# Schematic_easyeda.net
KiCad netlist of a schematic drawn in EasyEDA
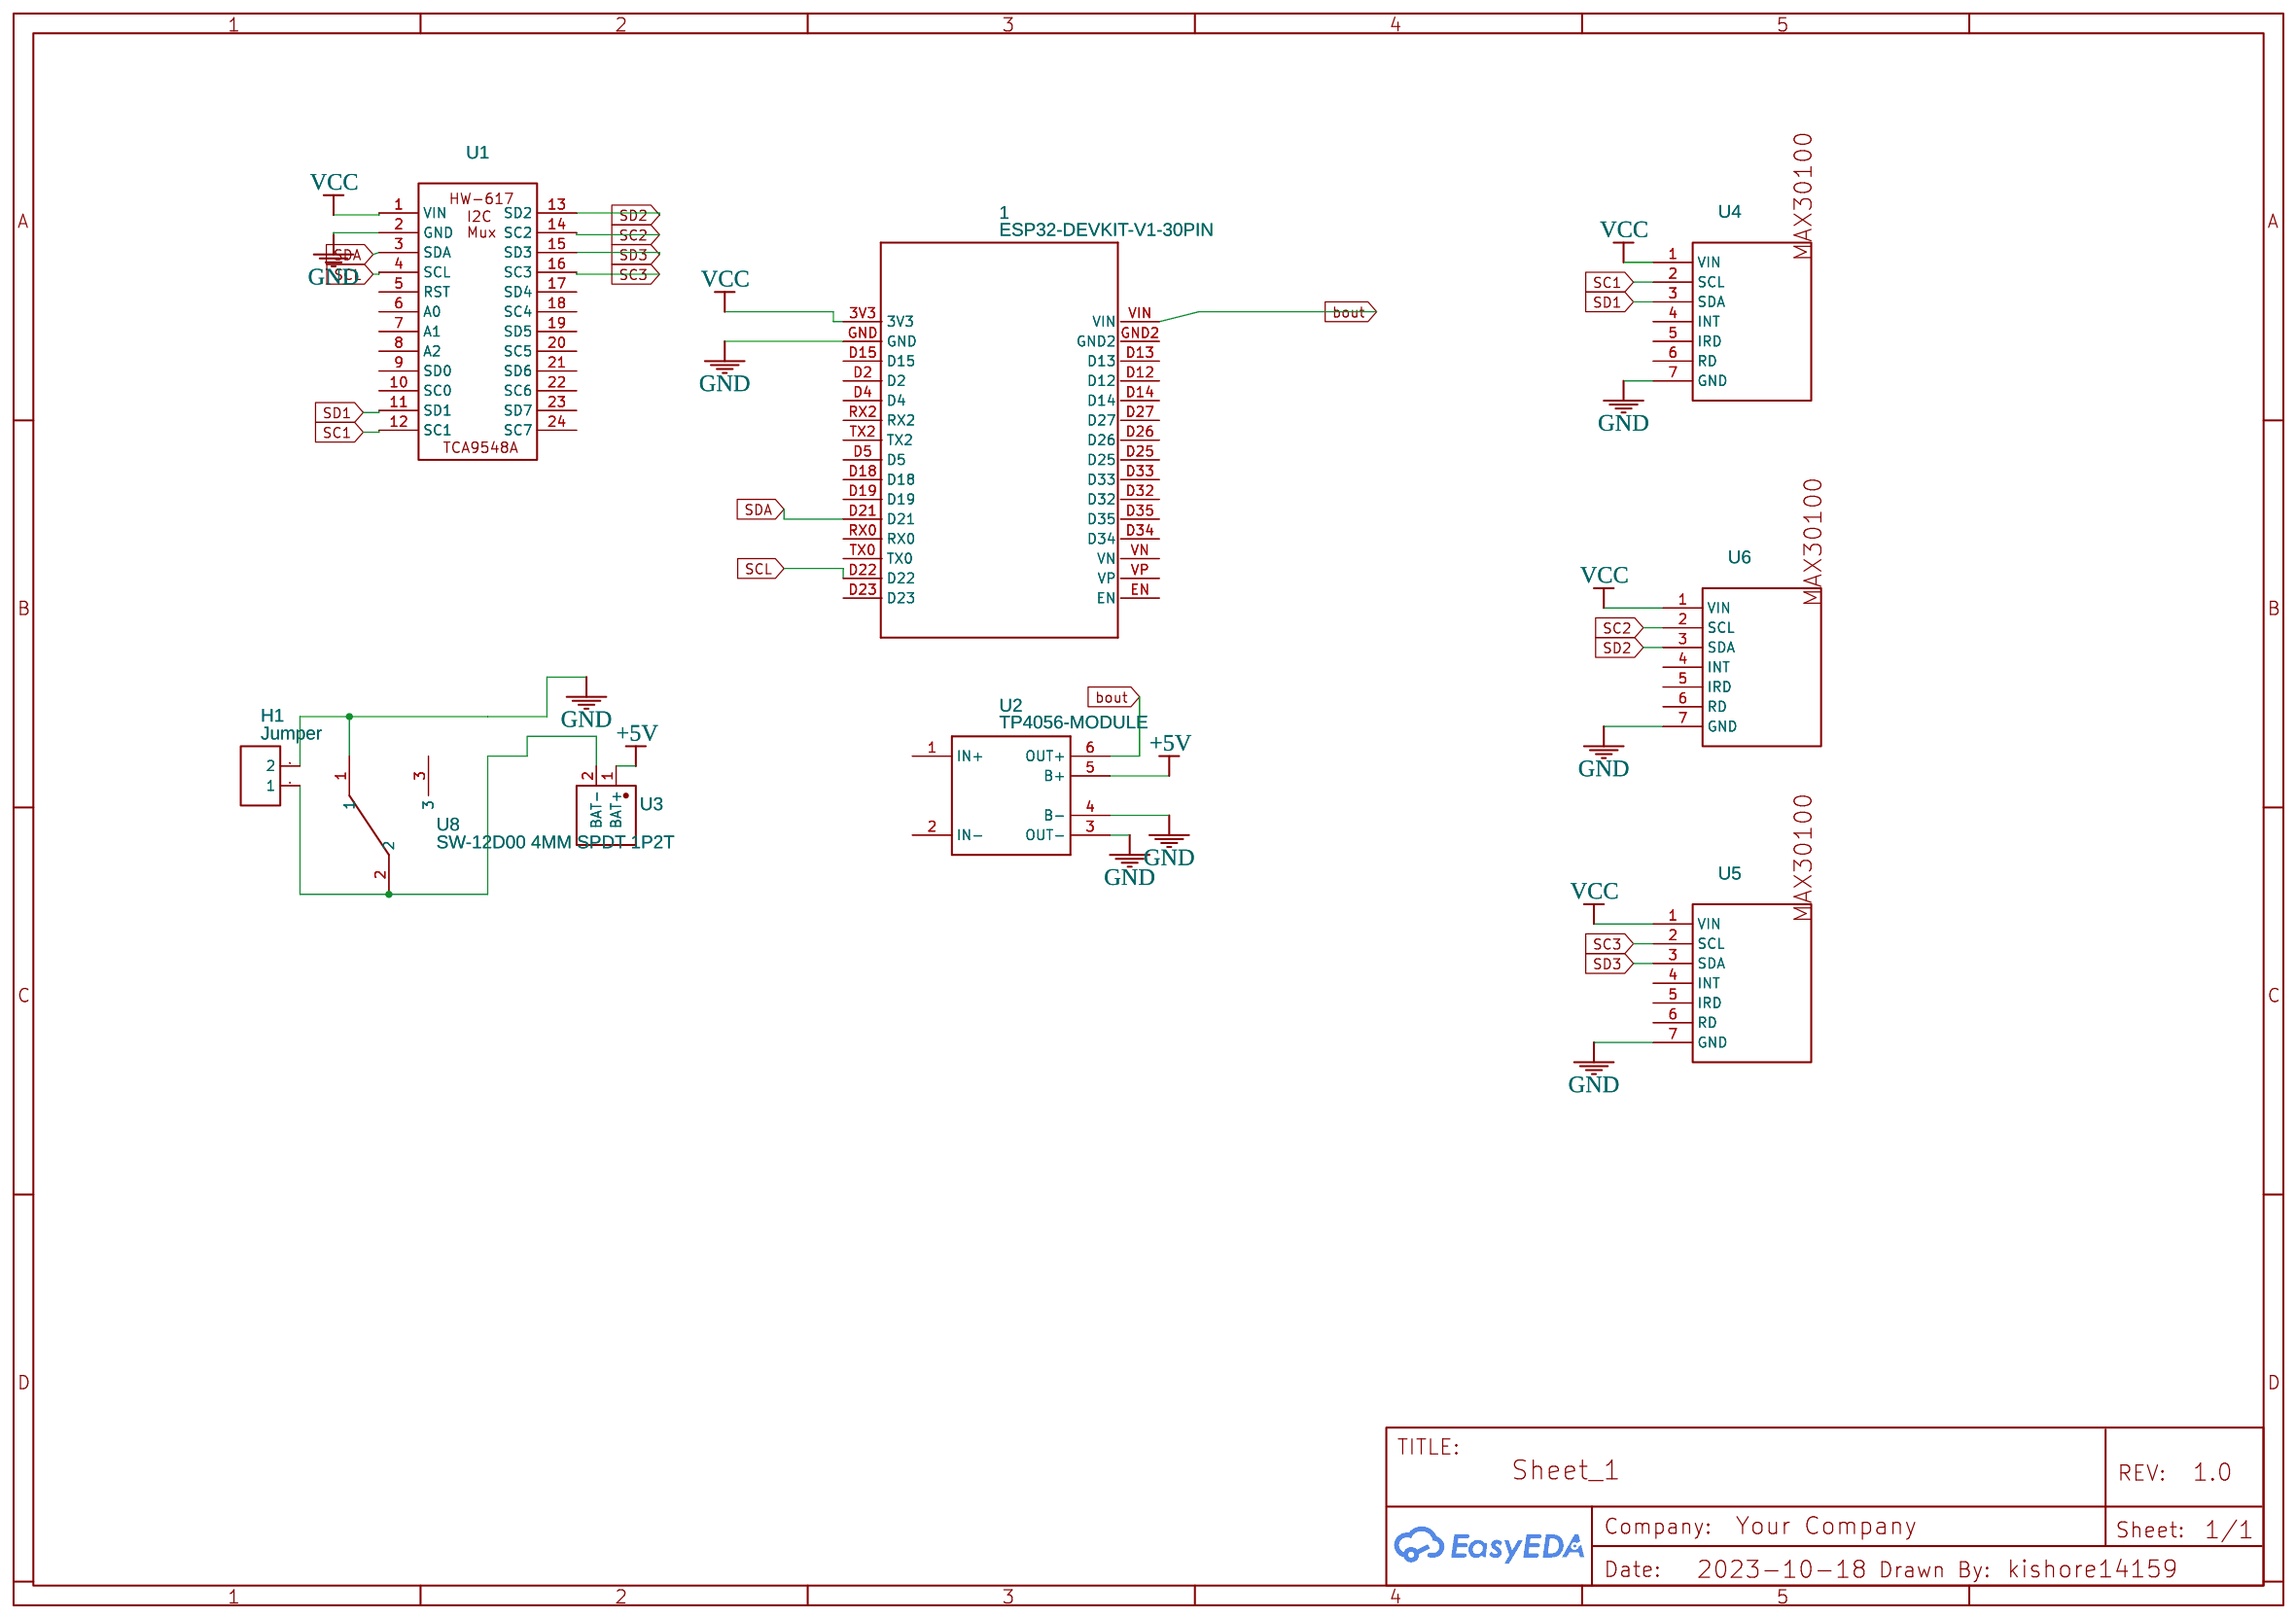
[diagram p0: schematic sheet]

(export (version "E")
  (design (tool "Eeschema 10.0.6"))
  (components
    (comp (ref "1") (value "ESP32-DEVKIT-V1-30PIN") (libsource (lib "") (part "ESP32-DEVKIT-V1-30PIN")))
    (comp (ref "H1") (value "Jumper") (libsource (lib "") (part "HDR-F-2.54_1x2")))
    (comp (ref "U1")
      (value "NO")
      (fields (field (name "Manufacturer Part") "TCA9548A") (field (name "Manufacturer") "Texas Instruments"))
      (libsource (lib "") (part "TCA9548A HW-617_OK"))
    )
    (comp (ref "U2") (value "TP4056-MODULE") (libsource (lib "") (part "TP4056-MODULE")))
    (comp (ref "U3") (value "NO") (libsource (lib "") (part "JST-PH-JST-PH2")))
    (comp (ref "U4") (value "NO") (libsource (lib "") (part "MAX30100 MODULE")))
    (comp (ref "U5") (value "NO") (libsource (lib "") (part "MAX30100 MODULE")))
    (comp (ref "U6") (value "NO") (libsource (lib "") (part "MAX30100 MODULE")))
    (comp (ref "U8") (value "SW-12D00 4MM SPDT 1P2T") (libsource (lib "") (part "SW-12D00 4MM SPDT 1P2T")))
  )
  (nets
    (net (code "1") (name "+5V") (class "Default")
      (node (ref "U2") (pin "5") (pinfunction "B+_5") (pintype "passive"))
      (node (ref "U3") (pin "1") (pinfunction "BAT+_1") (pintype "unspecified"))
    )
    (net (code "2") (name "GND") (class "Default")
      (node (ref "1") (pin "GND") (pinfunction "GND_GND") (pintype "bidirectional"))
      (node (ref "H1") (pin "2") (pinfunction "2_2") (pintype "input"))
      (node (ref "U1") (pin "2") (pinfunction "GND_2") (pintype "unspecified"))
      (node (ref "U2") (pin "3") (pinfunction "OUT-_3") (pintype "passive"))
      (node (ref "U2") (pin "4") (pinfunction "B-_4") (pintype "passive"))
      (node (ref "U4") (pin "7") (pinfunction "GND_7") (pintype "unspecified"))
      (node (ref "U5") (pin "7") (pinfunction "GND_7") (pintype "unspecified"))
      (node (ref "U6") (pin "7") (pinfunction "GND_7") (pintype "unspecified"))
      (node (ref "U8") (pin "1") (pinfunction "1_1") (pintype "unspecified"))
    )
    (net (code "3") (name "Net-(U3-BAT-)") (class "Default")
      (node (ref "H1") (pin "1") (pinfunction "1_1") (pintype "input"))
      (node (ref "U3") (pin "2") (pinfunction "BAT-_2") (pintype "unspecified"))
      (node (ref "U8") (pin "2") (pinfunction "2_2") (pintype "unspecified"))
    )
    (net (code "4") (name "SC1") (class "Default")
      (node (ref "U1") (pin "12") (pinfunction "SC1_12") (pintype "unspecified"))
      (node (ref "U4") (pin "2") (pinfunction "SCL_2") (pintype "unspecified"))
    )
    (net (code "5") (name "SC2") (class "Default")
      (node (ref "U1") (pin "14") (pinfunction "SC2_14") (pintype "unspecified"))
      (node (ref "U6") (pin "2") (pinfunction "SCL_2") (pintype "unspecified"))
    )
    (net (code "6") (name "SC3") (class "Default")
      (node (ref "U1") (pin "16") (pinfunction "SC3_16") (pintype "unspecified"))
      (node (ref "U5") (pin "2") (pinfunction "SCL_2") (pintype "unspecified"))
    )
    (net (code "7") (name "SCL") (class "Default")
      (node (ref "1") (pin "D22") (pinfunction "D22_D22") (pintype "bidirectional"))
      (node (ref "U1") (pin "4") (pinfunction "SCL_4") (pintype "unspecified"))
    )
    (net (code "8") (name "SD1") (class "Default")
      (node (ref "U1") (pin "11") (pinfunction "SD1_11") (pintype "unspecified"))
      (node (ref "U4") (pin "3") (pinfunction "SDA_3") (pintype "unspecified"))
    )
    (net (code "9") (name "SD2") (class "Default")
      (node (ref "U1") (pin "13") (pinfunction "SD2_13") (pintype "unspecified"))
      (node (ref "U6") (pin "3") (pinfunction "SDA_3") (pintype "unspecified"))
    )
    (net (code "10") (name "SD3") (class "Default")
      (node (ref "U1") (pin "15") (pinfunction "SD3_15") (pintype "unspecified"))
      (node (ref "U5") (pin "3") (pinfunction "SDA_3") (pintype "unspecified"))
    )
    (net (code "11") (name "SDA") (class "Default")
      (node (ref "1") (pin "D21") (pinfunction "D21_D21") (pintype "bidirectional"))
      (node (ref "U1") (pin "3") (pinfunction "SDA_3") (pintype "unspecified"))
    )
    (net (code "12") (name "VCC") (class "Default")
      (node (ref "1") (pin "3V3") (pinfunction "3V3_3V3") (pintype "bidirectional"))
      (node (ref "U1") (pin "1") (pinfunction "VIN_1") (pintype "unspecified"))
      (node (ref "U4") (pin "1") (pinfunction "VIN_1") (pintype "unspecified"))
      (node (ref "U5") (pin "1") (pinfunction "VIN_1") (pintype "unspecified"))
      (node (ref "U6") (pin "1") (pinfunction "VIN_1") (pintype "unspecified"))
    )
    (net (code "13") (name "bout") (class "Default")
      (node (ref "1") (pin "VIN") (pinfunction "VIN_VIN") (pintype "bidirectional"))
      (node (ref "U2") (pin "6") (pinfunction "OUT+_6") (pintype "passive"))
    )
    (net (code "14") (name "unconnected-(1-PadD2)") (class "Default")
      (node (ref "1") (pin "D2") (pinfunction "D2_D2") (pintype "bidirectional"))
    )
    (net (code "15") (name "unconnected-(1-PadD4)") (class "Default")
      (node (ref "1") (pin "D4") (pinfunction "D4_D4") (pintype "bidirectional"))
    )
    (net (code "16") (name "unconnected-(1-PadD5)") (class "Default")
      (node (ref "1") (pin "D5") (pinfunction "D5_D5") (pintype "bidirectional"))
    )
    (net (code "17") (name "unconnected-(1-PadD12)") (class "Default")
      (node (ref "1") (pin "D12") (pinfunction "D12_D12") (pintype "bidirectional"))
    )
    (net (code "18") (name "unconnected-(1-PadD13)") (class "Default")
      (node (ref "1") (pin "D13") (pinfunction "D13_D13") (pintype "bidirectional"))
    )
    (net (code "19") (name "unconnected-(1-PadD14)") (class "Default")
      (node (ref "1") (pin "D14") (pinfunction "D14_D14") (pintype "bidirectional"))
    )
    (net (code "20") (name "unconnected-(1-PadD15)") (class "Default")
      (node (ref "1") (pin "D15") (pinfunction "D15_D15") (pintype "bidirectional"))
    )
    (net (code "21") (name "unconnected-(1-PadD18)") (class "Default")
      (node (ref "1") (pin "D18") (pinfunction "D18_D18") (pintype "bidirectional"))
    )
    (net (code "22") (name "unconnected-(1-PadD19)") (class "Default")
      (node (ref "1") (pin "D19") (pinfunction "D19_D19") (pintype "bidirectional"))
    )
    (net (code "23") (name "unconnected-(1-PadD23)") (class "Default")
      (node (ref "1") (pin "D23") (pinfunction "D23_D23") (pintype "bidirectional"))
    )
    (net (code "24") (name "unconnected-(1-PadD25)") (class "Default")
      (node (ref "1") (pin "D25") (pinfunction "D25_D25") (pintype "bidirectional"))
    )
    (net (code "25") (name "unconnected-(1-PadD26)") (class "Default")
      (node (ref "1") (pin "D26") (pinfunction "D26_D26") (pintype "bidirectional"))
    )
    (net (code "26") (name "unconnected-(1-PadD27)") (class "Default")
      (node (ref "1") (pin "D27") (pinfunction "D27_D27") (pintype "bidirectional"))
    )
    (net (code "27") (name "unconnected-(1-PadD32)") (class "Default")
      (node (ref "1") (pin "D32") (pinfunction "D32_D32") (pintype "bidirectional"))
    )
    (net (code "28") (name "unconnected-(1-PadD33)") (class "Default")
      (node (ref "1") (pin "D33") (pinfunction "D33_D33") (pintype "bidirectional"))
    )
    (net (code "29") (name "unconnected-(1-PadD34)") (class "Default")
      (node (ref "1") (pin "D34") (pinfunction "D34_D34") (pintype "bidirectional"))
    )
    (net (code "30") (name "unconnected-(1-PadD35)") (class "Default")
      (node (ref "1") (pin "D35") (pinfunction "D35_D35") (pintype "bidirectional"))
    )
    (net (code "31") (name "unconnected-(1-PadEN)") (class "Default")
      (node (ref "1") (pin "EN") (pinfunction "EN_EN") (pintype "bidirectional"))
    )
    (net (code "32") (name "unconnected-(1-PadGND2)") (class "Default")
      (node (ref "1") (pin "GND2") (pinfunction "GND2_GND2") (pintype "bidirectional"))
    )
    (net (code "33") (name "unconnected-(1-PadRX0)") (class "Default")
      (node (ref "1") (pin "RX0") (pinfunction "RX0_RX0") (pintype "bidirectional"))
    )
    (net (code "34") (name "unconnected-(1-PadRX2)") (class "Default")
      (node (ref "1") (pin "RX2") (pinfunction "RX2_RX2") (pintype "bidirectional"))
    )
    (net (code "35") (name "unconnected-(1-PadTX0)") (class "Default")
      (node (ref "1") (pin "TX0") (pinfunction "TX0_TX0") (pintype "bidirectional"))
    )
    (net (code "36") (name "unconnected-(1-PadTX2)") (class "Default")
      (node (ref "1") (pin "TX2") (pinfunction "TX2_TX2") (pintype "bidirectional"))
    )
    (net (code "37") (name "unconnected-(1-PadVN)") (class "Default")
      (node (ref "1") (pin "VN") (pinfunction "VN_VN") (pintype "bidirectional"))
    )
    (net (code "38") (name "unconnected-(1-PadVP)") (class "Default")
      (node (ref "1") (pin "VP") (pinfunction "VP_VP") (pintype "bidirectional"))
    )
    (net (code "39") (name "unconnected-(U1-A0-Pad6)") (class "Default")
      (node (ref "U1") (pin "6") (pinfunction "A0_6") (pintype "unspecified"))
    )
    (net (code "40") (name "unconnected-(U1-A1-Pad7)") (class "Default")
      (node (ref "U1") (pin "7") (pinfunction "A1_7") (pintype "unspecified"))
    )
    (net (code "41") (name "unconnected-(U1-A2-Pad8)") (class "Default")
      (node (ref "U1") (pin "8") (pinfunction "A2_8") (pintype "unspecified"))
    )
    (net (code "42") (name "unconnected-(U1-RST-Pad5)") (class "Default")
      (node (ref "U1") (pin "5") (pinfunction "RST_5") (pintype "unspecified"))
    )
    (net (code "43") (name "unconnected-(U1-SC0-Pad10)") (class "Default")
      (node (ref "U1") (pin "10") (pinfunction "SC0_10") (pintype "unspecified"))
    )
    (net (code "44") (name "unconnected-(U1-SC4-Pad18)") (class "Default")
      (node (ref "U1") (pin "18") (pinfunction "SC4_18") (pintype "unspecified"))
    )
    (net (code "45") (name "unconnected-(U1-SC5-Pad20)") (class "Default")
      (node (ref "U1") (pin "20") (pinfunction "SC5_20") (pintype "unspecified"))
    )
    (net (code "46") (name "unconnected-(U1-SC6-Pad22)") (class "Default")
      (node (ref "U1") (pin "22") (pinfunction "SC6_22") (pintype "unspecified"))
    )
    (net (code "47") (name "unconnected-(U1-SC7-Pad24)") (class "Default")
      (node (ref "U1") (pin "24") (pinfunction "SC7_24") (pintype "unspecified"))
    )
    (net (code "48") (name "unconnected-(U1-SD0-Pad9)") (class "Default")
      (node (ref "U1") (pin "9") (pinfunction "SD0_9") (pintype "unspecified"))
    )
    (net (code "49") (name "unconnected-(U1-SD4-Pad17)") (class "Default")
      (node (ref "U1") (pin "17") (pinfunction "SD4_17") (pintype "unspecified"))
    )
    (net (code "50") (name "unconnected-(U1-SD5-Pad19)") (class "Default")
      (node (ref "U1") (pin "19") (pinfunction "SD5_19") (pintype "unspecified"))
    )
    (net (code "51") (name "unconnected-(U1-SD6-Pad21)") (class "Default")
      (node (ref "U1") (pin "21") (pinfunction "SD6_21") (pintype "unspecified"))
    )
    (net (code "52") (name "unconnected-(U1-SD7-Pad23)") (class "Default")
      (node (ref "U1") (pin "23") (pinfunction "SD7_23") (pintype "unspecified"))
    )
    (net (code "53") (name "unconnected-(U2-IN+-Pad1)") (class "Default")
      (node (ref "U2") (pin "1") (pinfunction "IN+_1") (pintype "passive"))
    )
    (net (code "54") (name "unconnected-(U2-IN--Pad2)") (class "Default")
      (node (ref "U2") (pin "2") (pinfunction "IN-_2") (pintype "passive"))
    )
    (net (code "55") (name "unconnected-(U4-INT-Pad4)") (class "Default")
      (node (ref "U4") (pin "4") (pinfunction "INT_4") (pintype "unspecified"))
    )
    (net (code "56") (name "unconnected-(U4-IRD-Pad5)") (class "Default")
      (node (ref "U4") (pin "5") (pinfunction "IRD_5") (pintype "unspecified"))
    )
    (net (code "57") (name "unconnected-(U4-RD-Pad6)") (class "Default")
      (node (ref "U4") (pin "6") (pinfunction "RD_6") (pintype "unspecified"))
    )
    (net (code "58") (name "unconnected-(U5-INT-Pad4)") (class "Default")
      (node (ref "U5") (pin "4") (pinfunction "INT_4") (pintype "unspecified"))
    )
    (net (code "59") (name "unconnected-(U5-IRD-Pad5)") (class "Default")
      (node (ref "U5") (pin "5") (pinfunction "IRD_5") (pintype "unspecified"))
    )
    (net (code "60") (name "unconnected-(U5-RD-Pad6)") (class "Default")
      (node (ref "U5") (pin "6") (pinfunction "RD_6") (pintype "unspecified"))
    )
    (net (code "61") (name "unconnected-(U6-INT-Pad4)") (class "Default")
      (node (ref "U6") (pin "4") (pinfunction "INT_4") (pintype "unspecified"))
    )
    (net (code "62") (name "unconnected-(U6-IRD-Pad5)") (class "Default")
      (node (ref "U6") (pin "5") (pinfunction "IRD_5") (pintype "unspecified"))
    )
    (net (code "63") (name "unconnected-(U6-RD-Pad6)") (class "Default")
      (node (ref "U6") (pin "6") (pinfunction "RD_6") (pintype "unspecified"))
    )
    (net (code "64") (name "unconnected-(U8-Pad3)") (class "Default")
      (node (ref "U8") (pin "3") (pinfunction "3_3") (pintype "unspecified"))
    )
  )
)
